# ID1.net
KiCad netlist of a schematic drawn in Altium Designer
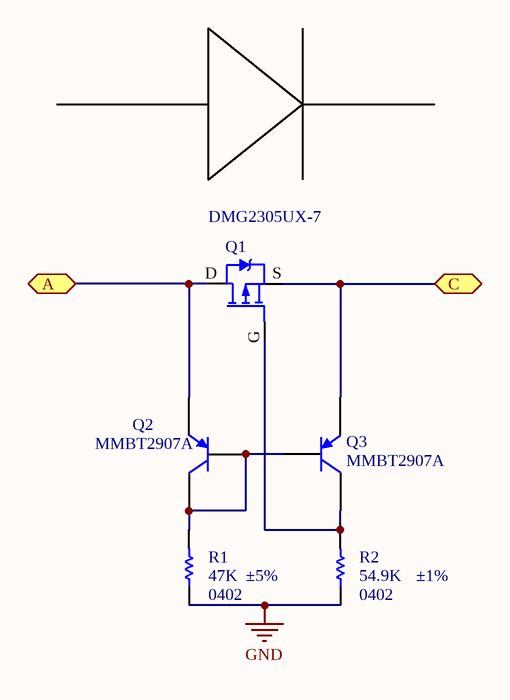
[diagram p0: ID1.SchDoc]

(export (version "E")
  (design (tool "Eeschema 10.0.6"))
  (components
    (comp (ref "Q1")
      (value "DMG2305UX")
      (footprint "DMG2305UX-7")
      (description "MOSFET P-CH 20V 4.2A SOT23")
      (fields
        (field (name "MANUFACTURER") "Diodes Incorporated")
        (field (name "MANUFACTURER PART NUMBER") "DMG2305UX-7")
        (field (name "CREATOR") "osman")
      )
      (libsource (lib "OLogic-Trans-Drivers") (part "DMG2305UX"))
    )
    (comp (ref "Q2")
      (value "MMBT2907A")
      (footprint "SOT23")
      (description "PNP General Purpose Amplifier")
      (fields (field (name "MANUFACTURER") "Fairchild Semiconductor"))
      (libsource (lib "OLogic-Trans-Drivers") (part "MMBT2907A"))
    )
    (comp (ref "Q3")
      (value "MMBT2907A")
      (footprint "SOT23")
      (description "PNP General Purpose Amplifier")
      (fields (field (name "MANUFACTURER") "Fairchild Semiconductor"))
      (libsource (lib "OLogic-Trans-Drivers") (part "MMBT2907A"))
    )
    (comp (ref "R1")
      (value "47K")
      (footprint "RESC0402(1005)_N")
      (description "47K 0402")
      (fields
        (field (name "MANUFACTURER") "Panasonic Electronic Components")
        (field (name "MANUFACTURER PART NUMBER") "ERJ-2GEJ473X")
        (field (name "TOLERANCE") "±5%")
        (field (name "SUPPLIER DEVICE PACKAGE") "0402")
      )
      (libsource (lib "OLogic-Passive") (part "RES 47K OHM 5% 1/10W 0402"))
    )
    (comp (ref "R2")
      (value "54.9K")
      (footprint "RESC0402(1005)_N")
      (description "54.9K 1% 0402")
      (fields
        (field (name "MANUFACTURER") "Panasonic Electronic Components")
        (field (name "MANUFACTURER PART NUMBER") "ERJ-2RKF5492X")
        (field (name "TOLERANCE") "±1%")
        (field (name "SUPPLIER DEVICE PACKAGE") "0402")
      )
      (libsource (lib "OLogic-Passive") (part "RES 54.9K OHM 1% 1/10W 0402"))
    )
  )
  (nets
    (net (code "1") (name "/A") (class "Default")
      (node (ref "Q1") (pin "D") (pinfunction "D_D") (pintype "passive"))
      (node (ref "Q2") (pin "2") (pinfunction "E_2") (pintype "passive"))
    )
    (net (code "2") (name "/C") (class "Default")
      (node (ref "Q1") (pin "S") (pinfunction "S_S") (pintype "passive"))
      (node (ref "Q3") (pin "2") (pinfunction "E_2") (pintype "passive"))
    )
    (net (code "3") (name "GND") (class "Default")
      (node (ref "R1") (pin "1") (pinfunction "1_1") (pintype "passive"))
      (node (ref "R2") (pin "1") (pinfunction "1_1") (pintype "passive"))
    )
    (net (code "4") (name "Net-(Q2-B)") (class "Default")
      (node (ref "Q2") (pin "1") (pinfunction "B_1") (pintype "passive"))
      (node (ref "Q2") (pin "3") (pinfunction "C_3") (pintype "passive"))
      (node (ref "Q3") (pin "1") (pinfunction "B_1") (pintype "passive"))
      (node (ref "R1") (pin "2") (pinfunction "2_2") (pintype "passive"))
    )
    (net (code "5") (name "Net-(Q3-C)") (class "Default")
      (node (ref "Q1") (pin "G") (pinfunction "G_G") (pintype "passive"))
      (node (ref "Q3") (pin "3") (pinfunction "C_3") (pintype "passive"))
      (node (ref "R2") (pin "2") (pinfunction "2_2") (pintype "passive"))
    )
  )
)
